# 06-CM4_USB_HDMI_SDCard.net
KiCad netlist of a schematic drawn in Altium Designer
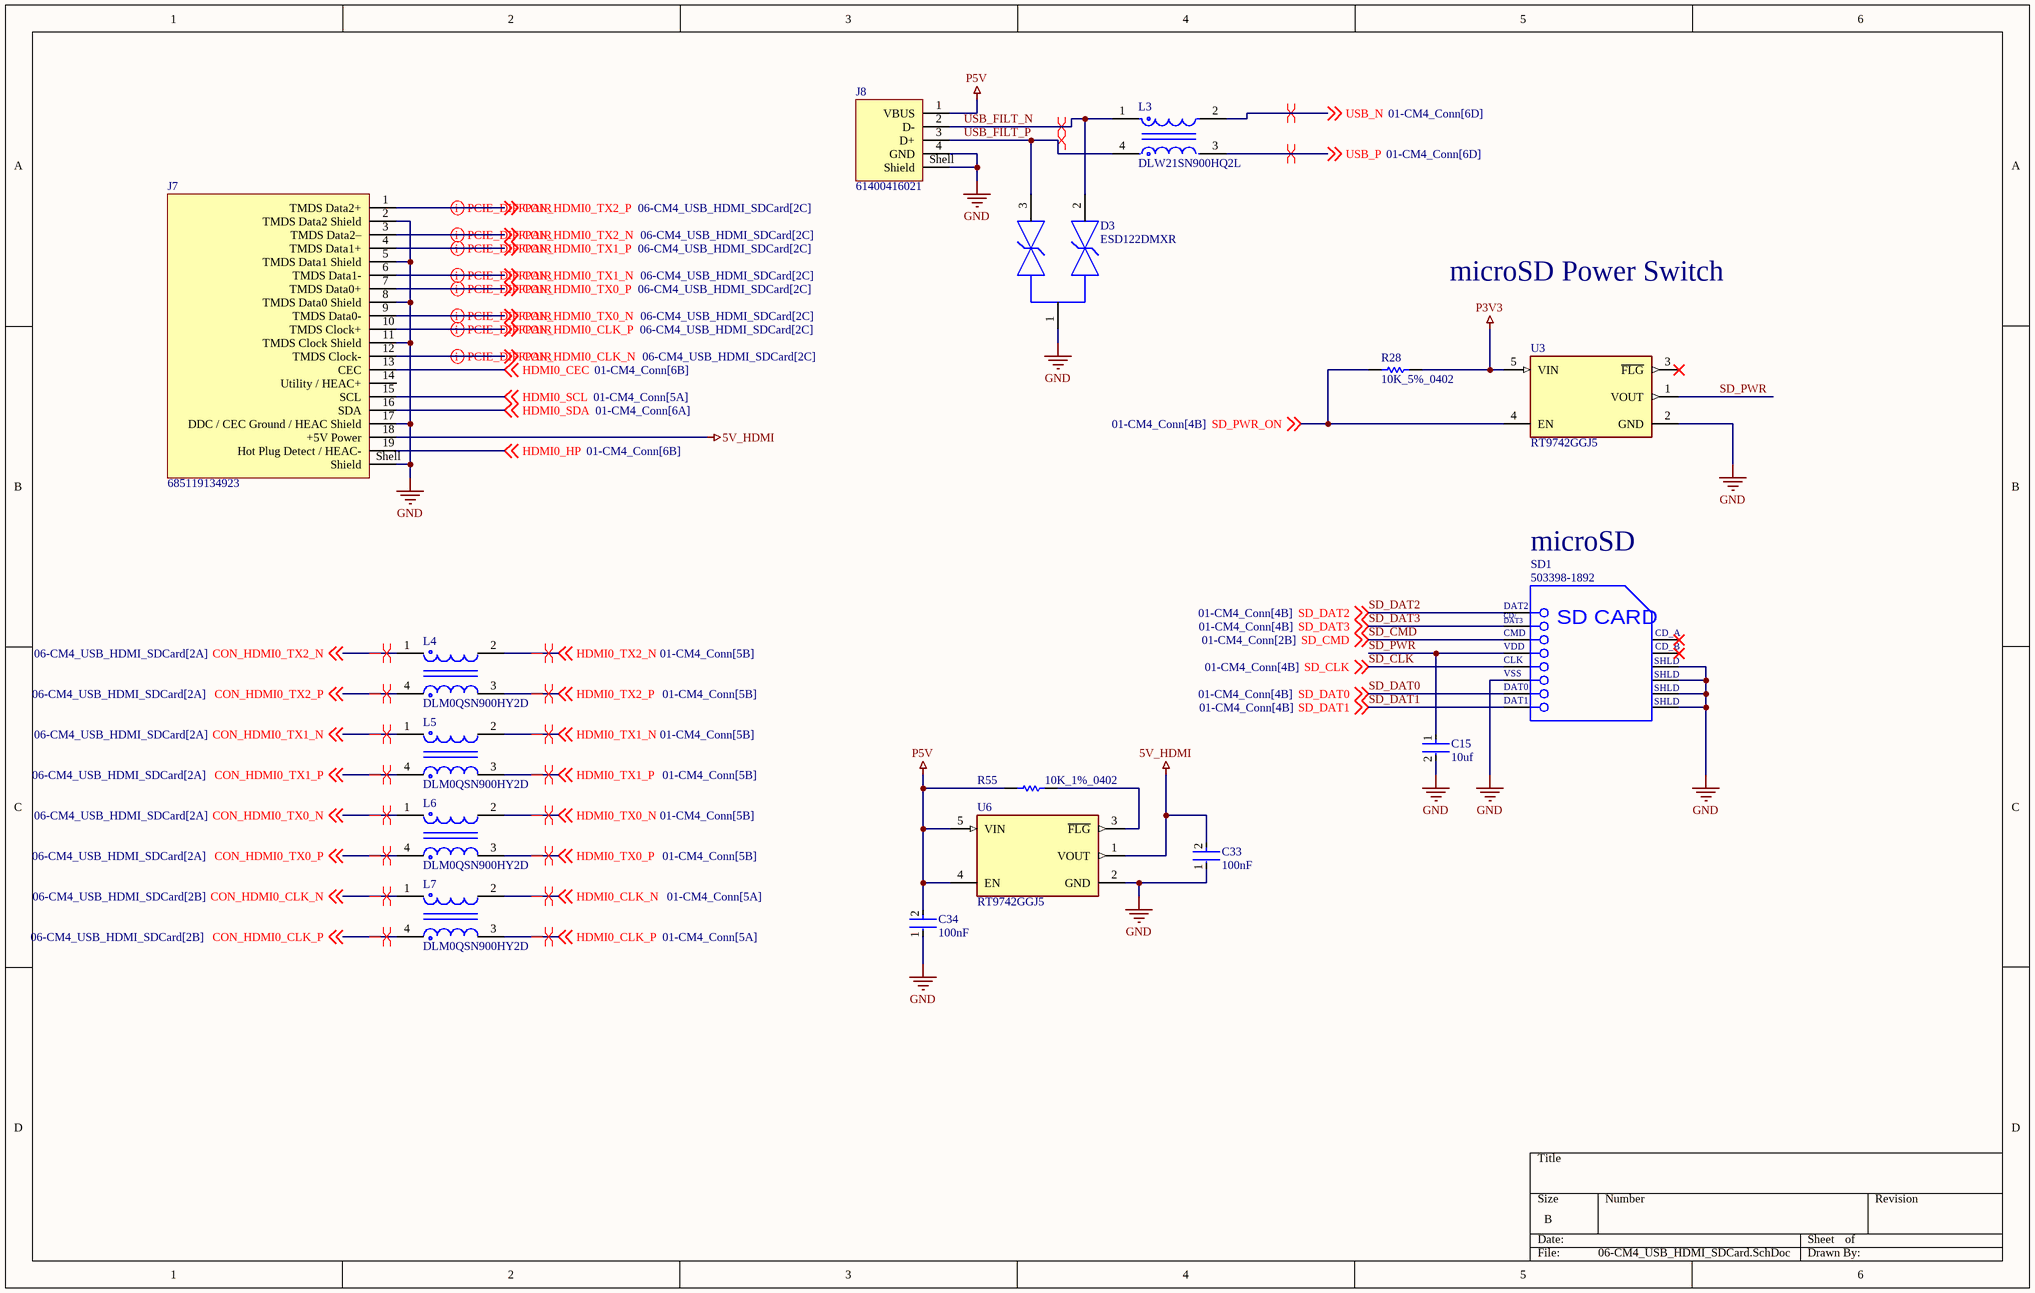
[diagram p0: 06-CM4_USB_HDMI_SDCard.SchDoc]

(export (version "E")
  (design (tool "Eeschema 10.0.6"))
  (components
    (comp (ref "C15")
      (value "10uf")
      (footprint "FP-GRM188-0_2-IPC_C")
      (description "Chip Multilayer Ceramic Capacitors for General Purpose, 0603, 10uF, X5R, 15%, 20%, 35V")
      (fields (field (name "TOLERANCE") "20%"))
      (libsource (lib "Altium Content Vault") (part "11868f565c42a9108669ba33697ecf6"))
    )
    (comp (ref "C33")
      (value "100nF")
      (footprint "FP-GRM15-MFG")
      (description "CAP CER 0.1UF 16V X7R 0402")
      (fields (field (name "MANUFACTURER PART NUMBER") "GRM155R71C104KA88D") (field (name "TOLERANCE") "10%"))
      (libsource (lib "Altium Content Vault") (part "236180d848d6139a670b325ea6854c9"))
    )
    (comp (ref "C34")
      (value "100nF")
      (footprint "FP-GRM15-MFG")
      (description "CAP CER 0.1UF 16V X7R 0402")
      (fields (field (name "MANUFACTURER PART NUMBER") "GRM155R71C104KA88D") (field (name "TOLERANCE") "10%"))
      (libsource (lib "Altium Content Vault") (part "236180d848d6139a670b325ea6854c9"))
    )
    (comp (ref "D3")
      (value "ESD122DMXR")
      (footprint "FP-DMX0003A-MFG")
      (description "TVS DIODE 3.6V 8.4V 3X2SON")
      (libsource (lib "Altium Content Vault") (part "7ac44b7b55cb7aaaff233ca2b760964"))
    )
    (comp (ref "J7")
      (value "685119134923")
      (footprint "685119134923")
      (libsource (lib "Altium Content Vault") (part "HDMI_Type A"))
    )
    (comp (ref "J8")
      (value "61400416021")
      (footprint "61400416021")
      (libsource (lib "Altium Content Vault") (part "USB 2.0_Type A_Receptacle_1 Port"))
    )
    (comp (ref "L3")
      (value "DLW21SN900HQ2L")
      (footprint "FP-DLW21S-MFG")
      (description "Common Mode Choke, 0805, 90Ω @ 100MHz, 0.41Ω, 25%, 280mA")
      (fields (field (name "TOLERANCE") "25%"))
      (libsource (lib "Altium Content Vault") (part "4bfa77fc51c2d0064063899a2a33d23"))
    )
    (comp (ref "L4")
      (value "DLM0QSN900HY2D")
      (footprint "FP-DLM0Q-MFG")
      (description "Chip Common Mode Choke Coil Monolithic 025020 50mA 90Ohm @ 100MHz")
      (libsource (lib "Altium Content Vault") (part "ceb18a25f7f751334f014c631ae0852"))
    )
    (comp (ref "L5")
      (value "DLM0QSN900HY2D")
      (footprint "FP-DLM0Q-MFG")
      (description "Chip Common Mode Choke Coil Monolithic 025020 50mA 90Ohm @ 100MHz")
      (libsource (lib "Altium Content Vault") (part "ceb18a25f7f751334f014c631ae0852"))
    )
    (comp (ref "L6")
      (value "DLM0QSN900HY2D")
      (footprint "FP-DLM0Q-MFG")
      (description "Chip Common Mode Choke Coil Monolithic 025020 50mA 90Ohm @ 100MHz")
      (libsource (lib "Altium Content Vault") (part "ceb18a25f7f751334f014c631ae0852"))
    )
    (comp (ref "L7")
      (value "DLM0QSN900HY2D")
      (footprint "FP-DLM0Q-MFG")
      (description "Chip Common Mode Choke Coil Monolithic 025020 50mA 90Ohm @ 100MHz")
      (libsource (lib "Altium Content Vault") (part "ceb18a25f7f751334f014c631ae0852"))
    )
    (comp (ref "R28")
      (value "10K_5%_0402")
      (footprint "RESC1005X40X25ML05T05")
      (fields (field (name "PART NUMBER") "ERJ-2GEJ103X") (field (name "MANUFACTURER") "Panasonic"))
      (libsource (lib "Altium Content Vault") (part "RES"))
    )
    (comp (ref "R55")
      (value "10K_1%_0402")
      (footprint "RESC1005X40X25NL10T10")
      (fields (field (name "MANUFACTURER") "Bourns") (field (name "PART NUMBER") "CR0402-FX-1002GLF"))
      (libsource (lib "Altium Content Vault") (part "RES"))
    )
    (comp (ref "SD1")
      (value "503398-1892")
      (footprint "MOLX-503398-1892_V")
      (description "Micro SD Connector, Pitch 1.1 mm, 8 Position, Height 1.4 mm, -25 to 85 degC, RoHS, Tape and Reel")
      (fields (field (name "MANUFACTURER") "Molex"))
      (libsource (lib "Altium Content Vault") (part "CN-SD-8-2SW-4S"))
    )
    (comp (ref "U3")
      (value "RT9742GGJ5")
      (footprint "FP-RT9742GGJ5-IPC_C")
      (description "IC PWR SWTCH N-CHAN 1:1 TSOT23-5")
      (libsource (lib "Altium Content Vault") (part "6b3db7b45087fee8fb60b49bef92a32"))
    )
    (comp (ref "U6")
      (value "RT9742GGJ5")
      (footprint "FP-RT9742GGJ5-IPC_C")
      (description "IC PWR SWTCH N-CHAN 1:1 TSOT23-5")
      (libsource (lib "Altium Content Vault") (part "6b3db7b45087fee8fb60b49bef92a32"))
    )
  )
  (nets
    (net (code "1") (name "/SD_PWR") (class "Default")
      (node (ref "C15") (pin "1") (pinfunction "1_1") (pintype "passive"))
      (node (ref "SD1") (pin "4") (pinfunction "VDD_4") (pintype "passive"))
      (node (ref "U3") (pin "1") (pinfunction "VOUT_1") (pintype "output"))
    )
    (net (code "2") (name "/USB_FILT_N") (class "Default")
      (node (ref "D3") (pin "2") (pinfunction "IO1_2") (pintype "passive"))
      (node (ref "J8") (pin "2") (pinfunction "D-_2") (pintype "passive"))
      (node (ref "L3") (pin "1") (pinfunction "1_1") (pintype "passive"))
    )
    (net (code "3") (name "/USB_FILT_P") (class "Default")
      (node (ref "D3") (pin "3") (pinfunction "IO2_3") (pintype "passive"))
      (node (ref "J8") (pin "3") (pinfunction "D+_3") (pintype "passive"))
      (node (ref "L3") (pin "4") (pinfunction "4_4") (pintype "passive"))
    )
    (net (code "4") (name "5V_HDMI") (class "Default")
      (node (ref "C33") (pin "2") (pinfunction "2_2") (pintype "passive"))
      (node (ref "J7") (pin "18") (pinfunction "+5V_Power_18") (pintype "passive"))
      (node (ref "U6") (pin "1") (pinfunction "VOUT_1") (pintype "output"))
    )
    (net (code "5") (name "CON_HDMI0_CLK_N") (class "Default")
      (node (ref "J7") (pin "12") (pinfunction "TMDS_Clock-_12") (pintype "passive"))
      (node (ref "L7") (pin "1") (pinfunction "1_1") (pintype "passive"))
    )
    (net (code "6") (name "CON_HDMI0_CLK_P") (class "Default")
      (node (ref "J7") (pin "10") (pinfunction "TMDS_Clock+_10") (pintype "passive"))
      (node (ref "L7") (pin "4") (pinfunction "4_4") (pintype "passive"))
    )
    (net (code "7") (name "CON_HDMI0_TX0_N") (class "Default")
      (node (ref "J7") (pin "9") (pinfunction "TMDS_Data0-_9") (pintype "passive"))
      (node (ref "L6") (pin "1") (pinfunction "1_1") (pintype "passive"))
    )
    (net (code "8") (name "CON_HDMI0_TX0_P") (class "Default")
      (node (ref "J7") (pin "7") (pinfunction "TMDS_Data0+_7") (pintype "passive"))
      (node (ref "L6") (pin "4") (pinfunction "4_4") (pintype "passive"))
    )
    (net (code "9") (name "CON_HDMI0_TX1_N") (class "Default")
      (node (ref "J7") (pin "6") (pinfunction "TMDS_Data1-_6") (pintype "passive"))
      (node (ref "L5") (pin "1") (pinfunction "1_1") (pintype "passive"))
    )
    (net (code "10") (name "CON_HDMI0_TX1_P") (class "Default")
      (node (ref "J7") (pin "4") (pinfunction "TMDS_Data1+_4") (pintype "passive"))
      (node (ref "L5") (pin "4") (pinfunction "4_4") (pintype "passive"))
    )
    (net (code "11") (name "CON_HDMI0_TX2_N") (class "Default")
      (node (ref "J7") (pin "3") (pinfunction "TMDS_Data2–_3") (pintype "passive"))
      (node (ref "L4") (pin "1") (pinfunction "1_1") (pintype "passive"))
    )
    (net (code "12") (name "CON_HDMI0_TX2_P") (class "Default")
      (node (ref "J7") (pin "1") (pinfunction "TMDS_Data2+_1") (pintype "passive"))
      (node (ref "L4") (pin "4") (pinfunction "4_4") (pintype "passive"))
    )
    (net (code "13") (name "GND") (class "Default")
      (node (ref "C15") (pin "2") (pinfunction "2_2") (pintype "passive"))
      (node (ref "C33") (pin "1") (pinfunction "1_1") (pintype "passive"))
      (node (ref "C34") (pin "1") (pinfunction "1_1") (pintype "passive"))
      (node (ref "D3") (pin "1") (pinfunction "GND_1") (pintype "power_in"))
      (node (ref "J7") (pin "11") (pinfunction "TMDS_Clock_Shield_11") (pintype "passive"))
      (node (ref "J7") (pin "17") (pinfunction "DDC_/_CEC_Ground_/_HEAC_Shield_17") (pintype "passive"))
      (node (ref "J7") (pin "2") (pinfunction "TMDS_Data2_Shield_2") (pintype "passive"))
      (node (ref "J7") (pin "5") (pinfunction "TMDS_Data1_Shield_5") (pintype "passive"))
      (node (ref "J7") (pin "8") (pinfunction "TMDS_Data0_Shield_8") (pintype "passive"))
      (node (ref "J7") (pin "Shell") (pinfunction "Shield_Shell") (pintype "passive"))
      (node (ref "J8") (pin "4") (pinfunction "GND_4") (pintype "passive"))
      (node (ref "J8") (pin "Shell") (pinfunction "Shield_Shell") (pintype "passive"))
      (node (ref "SD1") (pin "11") (pinfunction "SHLD_11") (pintype "passive"))
      (node (ref "SD1") (pin "12") (pinfunction "SHLD_12") (pintype "passive"))
      (node (ref "SD1") (pin "13") (pinfunction "SHLD_13") (pintype "passive"))
      (node (ref "SD1") (pin "14") (pinfunction "SHLD_14") (pintype "passive"))
      (node (ref "SD1") (pin "6") (pinfunction "VSS_6") (pintype "passive"))
      (node (ref "U3") (pin "2") (pinfunction "GND_2") (pintype "power_in"))
      (node (ref "U6") (pin "2") (pinfunction "GND_2") (pintype "power_in"))
    )
    (net (code "14") (name "HDMI0_CEC") (class "Default")
      (node (ref "J7") (pin "13") (pinfunction "CEC_13") (pintype "passive"))
    )
    (net (code "15") (name "HDMI0_CLK_N") (class "Default")
      (node (ref "L7") (pin "2") (pinfunction "2_2") (pintype "passive"))
    )
    (net (code "16") (name "HDMI0_CLK_P") (class "Default")
      (node (ref "L7") (pin "3") (pinfunction "3_3") (pintype "passive"))
    )
    (net (code "17") (name "HDMI0_HP") (class "Default")
      (node (ref "J7") (pin "19") (pinfunction "Hot_Plug_Detect_/_HEAC-_19") (pintype "passive"))
    )
    (net (code "18") (name "HDMI0_SCL") (class "Default")
      (node (ref "J7") (pin "15") (pinfunction "SCL_15") (pintype "passive"))
    )
    (net (code "19") (name "HDMI0_SDA") (class "Default")
      (node (ref "J7") (pin "16") (pinfunction "SDA_16") (pintype "passive"))
    )
    (net (code "20") (name "HDMI0_TX0_N") (class "Default")
      (node (ref "L6") (pin "2") (pinfunction "2_2") (pintype "passive"))
    )
    (net (code "21") (name "HDMI0_TX0_P") (class "Default")
      (node (ref "L6") (pin "3") (pinfunction "3_3") (pintype "passive"))
    )
    (net (code "22") (name "HDMI0_TX1_N") (class "Default")
      (node (ref "L5") (pin "2") (pinfunction "2_2") (pintype "passive"))
    )
    (net (code "23") (name "HDMI0_TX1_P") (class "Default")
      (node (ref "L5") (pin "3") (pinfunction "3_3") (pintype "passive"))
    )
    (net (code "24") (name "HDMI0_TX2_N") (class "Default")
      (node (ref "L4") (pin "2") (pinfunction "2_2") (pintype "passive"))
    )
    (net (code "25") (name "HDMI0_TX2_P") (class "Default")
      (node (ref "L4") (pin "3") (pinfunction "3_3") (pintype "passive"))
    )
    (net (code "26") (name "Net-(U6-~{FLG})") (class "Default")
      (node (ref "R55") (pin "2") (pinfunction "2_2") (pintype "passive"))
      (node (ref "U6") (pin "3") (pinfunction "~{FLG}_3") (pintype "output"))
    )
    (net (code "27") (name "P3V3") (class "Default")
      (node (ref "R28") (pin "2") (pinfunction "2_2") (pintype "passive"))
      (node (ref "U3") (pin "5") (pinfunction "VIN_5") (pintype "input"))
    )
    (net (code "28") (name "P5V") (class "Default")
      (node (ref "C34") (pin "2") (pinfunction "2_2") (pintype "passive"))
      (node (ref "J8") (pin "1") (pinfunction "VBUS_1") (pintype "passive"))
      (node (ref "R55") (pin "1") (pinfunction "1_1") (pintype "passive"))
      (node (ref "U6") (pin "4") (pinfunction "EN_4") (pintype "passive"))
      (node (ref "U6") (pin "5") (pinfunction "VIN_5") (pintype "input"))
    )
    (net (code "29") (name "SD_CLK") (class "Default")
      (node (ref "SD1") (pin "5") (pinfunction "CLK_5") (pintype "passive"))
    )
    (net (code "30") (name "SD_CMD") (class "Default")
      (node (ref "SD1") (pin "3") (pinfunction "CMD_3") (pintype "passive"))
    )
    (net (code "31") (name "SD_DAT0") (class "Default")
      (node (ref "SD1") (pin "7") (pinfunction "DAT0_7") (pintype "passive"))
    )
    (net (code "32") (name "SD_DAT1") (class "Default")
      (node (ref "SD1") (pin "8") (pinfunction "DAT1_8") (pintype "passive"))
    )
    (net (code "33") (name "SD_DAT2") (class "Default")
      (node (ref "SD1") (pin "1") (pinfunction "DAT2_1") (pintype "passive"))
    )
    (net (code "34") (name "SD_DAT3") (class "Default")
      (node (ref "SD1") (pin "2") (pinfunction "CD/DAT3_2") (pintype "passive"))
    )
    (net (code "35") (name "SD_PWR_ON") (class "Default")
      (node (ref "R28") (pin "1") (pinfunction "1_1") (pintype "passive"))
      (node (ref "U3") (pin "4") (pinfunction "EN_4") (pintype "passive"))
    )
    (net (code "36") (name "USB_N") (class "Default")
      (node (ref "L3") (pin "2") (pinfunction "2_2") (pintype "passive"))
    )
    (net (code "37") (name "USB_P") (class "Default")
      (node (ref "L3") (pin "3") (pinfunction "3_3") (pintype "passive"))
    )
    (net (code "38") (name "unconnected-(J7-Utility_{slash}_HEAC+-Pad14)") (class "Default")
      (node (ref "J7") (pin "14") (pinfunction "Utility_/_HEAC+_14") (pintype "passive"))
    )
    (net (code "39") (name "unconnected-(SD1-CD_A-Pad9)") (class "Default")
      (node (ref "SD1") (pin "9") (pinfunction "CD_A_9") (pintype "passive+no_connect"))
    )
    (net (code "40") (name "unconnected-(SD1-CD_B-Pad10)") (class "Default")
      (node (ref "SD1") (pin "10") (pinfunction "CD_B_10") (pintype "passive+no_connect"))
    )
    (net (code "41") (name "unconnected-(U3-~{FLG}-Pad3)") (class "Default")
      (node (ref "U3") (pin "3") (pinfunction "~{FLG}_3") (pintype "output+no_connect"))
    )
  )
)
